# H18R10.net
KiCad netlist of a schematic drawn in EAGLE
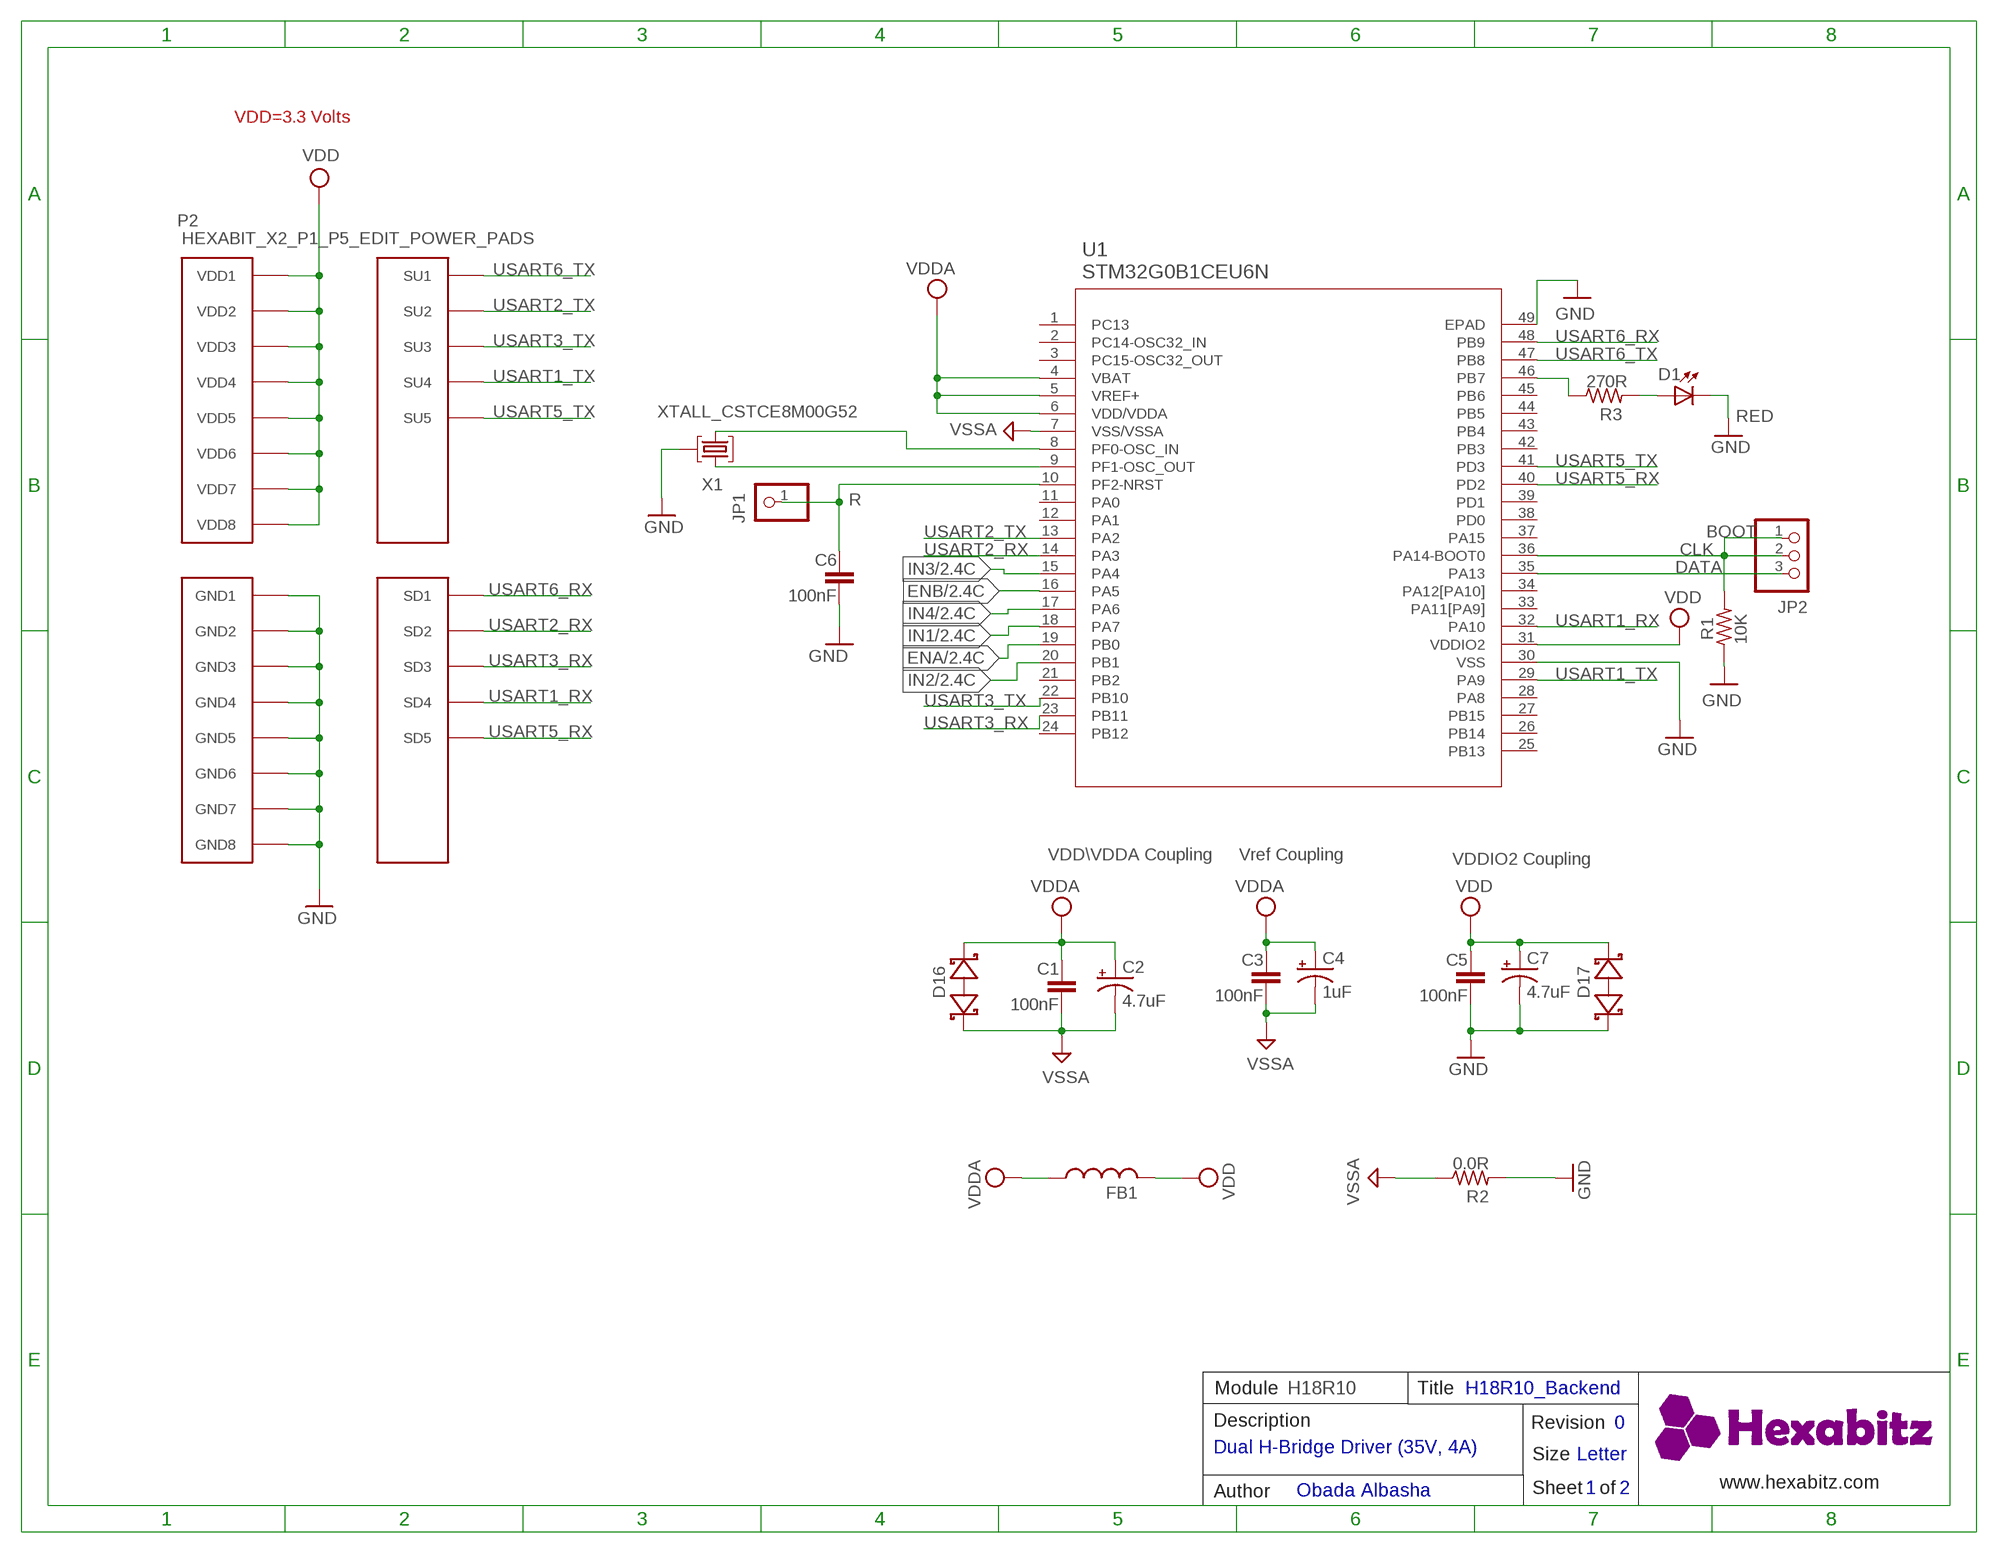
[diagram p0: schematic, sheet 1]
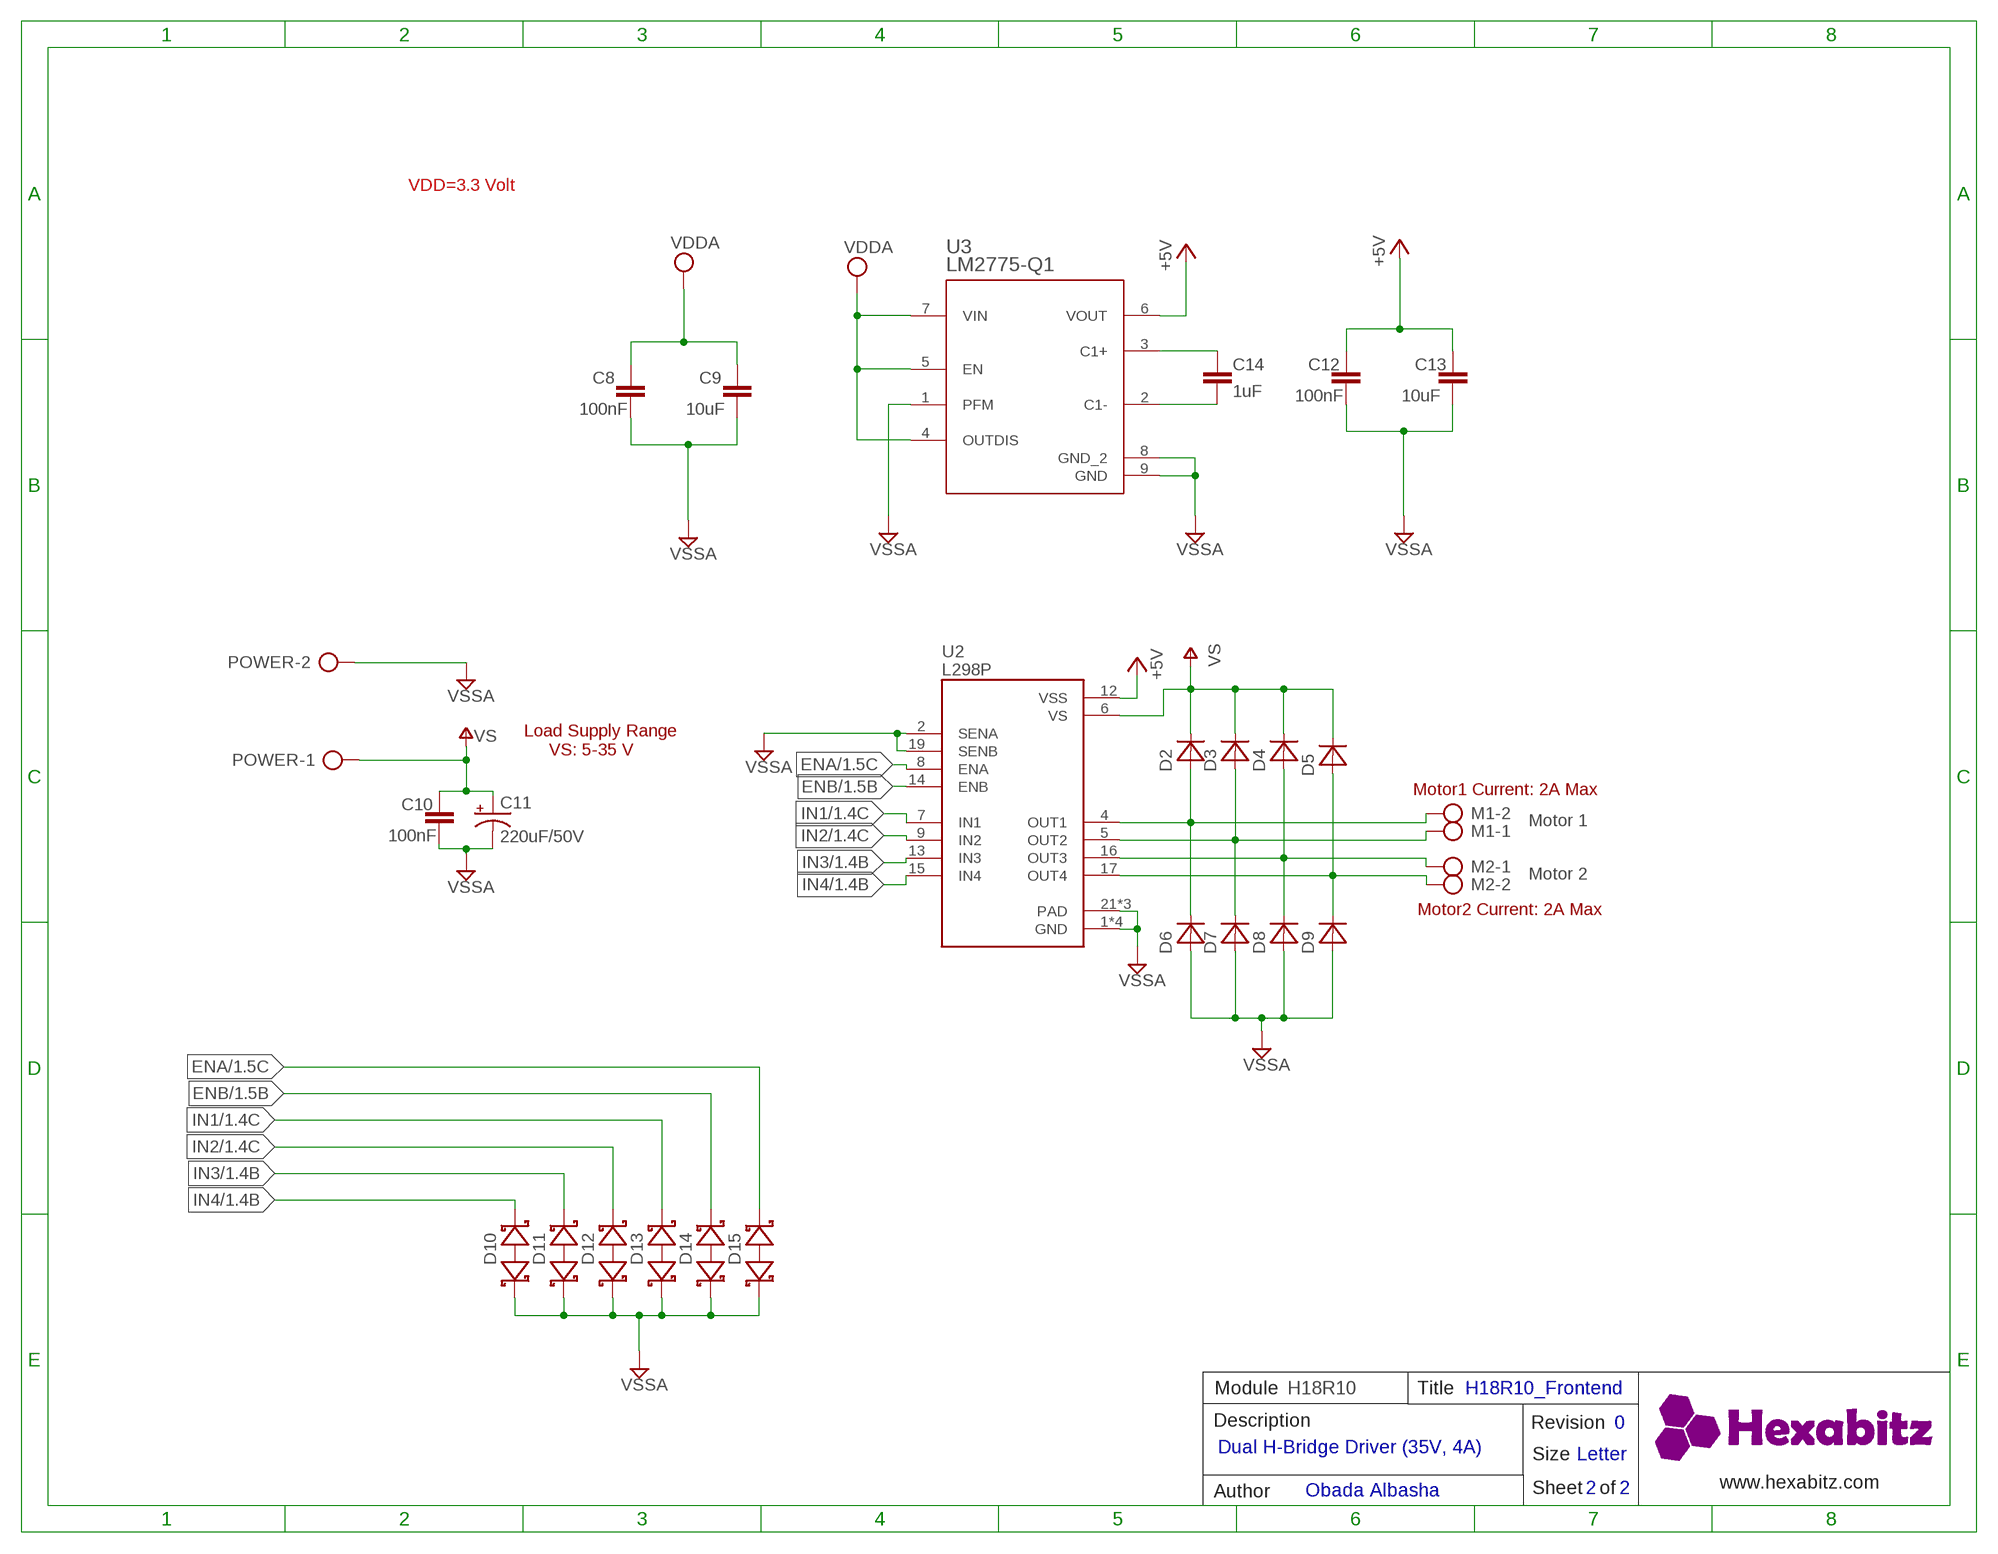
[diagram p1: schematic, sheet 2]

(export (version "E")
  (design (tool "Eeschema 10.0.6"))
  (components
    (comp (ref "C1")
      (value "100nF")
      (footprint "eagle-import:C-0603")
      (libsource (lib "eagle-import") (part "C-0603"))
    )
    (comp (ref "C2")
      (value "4.7uF")
      (footprint "eagle-import:C-0805-POL")
      (libsource (lib "eagle-import") (part "C-0805-POL"))
    )
    (comp (ref "C3")
      (value "100nF")
      (footprint "eagle-import:C-0603")
      (libsource (lib "eagle-import") (part "C-0603"))
    )
    (comp (ref "C4")
      (value "1uF")
      (footprint "eagle-import:C-0805-POL")
      (libsource (lib "eagle-import") (part "C-0805-POL"))
    )
    (comp (ref "C5")
      (value "100nF")
      (footprint "eagle-import:C-0603")
      (libsource (lib "eagle-import") (part "C-0603"))
    )
    (comp (ref "C6")
      (value "100nF")
      (footprint "eagle-import:C-0603")
      (libsource (lib "eagle-import") (part "C-0603"))
    )
    (comp (ref "C7")
      (value "4.7uF")
      (footprint "eagle-import:C-0805-POL")
      (libsource (lib "eagle-import") (part "C-0805-POL"))
    )
    (comp (ref "D1")
      (value "RED")
      (footprint "eagle-import:VLMS1300-GS08")
      (fields
        (field (name "MPN") "VLMS1300-GS08")
        (field (name "MFN") "Vishay")
        (field (name "MPN_1") "VLMS1300-GS08")
        (field (name "OCTOPART_URL") "https://octopart.com/vlms1300-gs08-vishay-21709201?r=sp&s=_gcP4_q8T1SC6PJQPTQ9yA")
      )
      (libsource (lib "eagle-import") (part "VLMS1300-GS08"))
    )
    (comp (ref "D16")
      (value "BOURNS_CDSOD323-T03SCBOURNS_CDSOD323-T03SC_0_0")
      (footprint "eagle-import:BOURNS_CDSOD323-T03SC_0")
      (fields (field (name "MPN") "CDSOD323-T03SC"))
      (libsource (lib "eagle-import") (part "BOURNS_CDSOD323-T03SCBOURNS_CDSOD323-T03SC_0_0"))
    )
    (comp (ref "D17")
      (value "BOURNS_CDSOD323-T03SCBOURNS_CDSOD323-T03SC_0_0")
      (footprint "eagle-import:BOURNS_CDSOD323-T03SC_0")
      (fields (field (name "MPN") "CDSOD323-T03SC"))
      (libsource (lib "eagle-import") (part "BOURNS_CDSOD323-T03SCBOURNS_CDSOD323-T03SC_0_0"))
    )
    (comp (ref "FB1")
      (value "FB-0603")
      (footprint "eagle-import:FB-0603")
      (libsource (lib "eagle-import") (part "FB-0603"))
    )
    (comp (ref "JP1")
      (value "R")
      (footprint "eagle-import:1X01")
      (fields (field (name "MPN") "87227-1"))
      (libsource (lib "eagle-import") (part "PINHD-1X1"))
    )
    (comp (ref "JP2")
      (value "PINHD-1X3")
      (footprint "eagle-import:1X03")
      (libsource (lib "eagle-import") (part "PINHD-1X3"))
    )
    (comp (ref "P2")
      (value "HEXABIT_X2_P1_P5_EDIT_POWER_PADS")
      (footprint "eagle-import:HEXABIT_X2_P1_P5_EDIT_POWER_PADS")
      (libsource (lib "eagle-import") (part "HEXABIT_X2_P1_P5_EDIT_POWER_PADS"))
    )
    (comp (ref "R1")
      (value "10K")
      (footprint "eagle-import:R-0603")
      (libsource (lib "eagle-import") (part "R-0603"))
    )
    (comp (ref "R2")
      (value "0.0R")
      (footprint "eagle-import:R-0603")
      (libsource (lib "eagle-import") (part "R-0603"))
    )
    (comp (ref "R3")
      (value "270R")
      (footprint "eagle-import:R-0603")
      (libsource (lib "eagle-import") (part "R-0603"))
    )
    (comp (ref "U1")
      (value "STM32G0B1CEU6N")
      (footprint "eagle-import:HEXABITZ_ICS_QFN_B1CEU6_STM-L")
      (libsource (lib "eagle-import") (part "STM32G0B1CEU6N"))
    )
    (comp (ref "X1")
      (value "XTALL_CSTCE8M00G52")
      (footprint "eagle-import:XTALL_CSTCE8M00G52")
      (fields (field (name "MPN") "CSTCE8M00G52Z-R0"))
      (libsource (lib "eagle-import") (part "XTALL_CSTCE8M00G52"))
    )
    (comp (ref "C8")
      (value "100nF")
      (footprint "eagle-import:C-0603")
      (libsource (lib "eagle-import") (part "C-0603"))
    )
    (comp (ref "C9")
      (value "10uF")
      (footprint "eagle-import:C-0603")
      (libsource (lib "eagle-import") (part "C-0603"))
    )
    (comp (ref "C10")
      (value "100nF")
      (footprint "eagle-import:C-0603")
      (libsource (lib "eagle-import") (part "C-0603"))
    )
    (comp (ref "C11")
      (value "220uF/50V")
      (footprint "eagle-import:TT5D10")
      (libsource (lib "eagle-import") (part "CPOL-USTT5D10"))
    )
    (comp (ref "C12")
      (value "100nF")
      (footprint "eagle-import:C-0603")
      (libsource (lib "eagle-import") (part "C-0603"))
    )
    (comp (ref "C13")
      (value "10uF")
      (footprint "eagle-import:C-0603")
      (libsource (lib "eagle-import") (part "C-0603"))
    )
    (comp (ref "C14")
      (value "1uF")
      (footprint "eagle-import:C-0603")
      (libsource (lib "eagle-import") (part "C-0603"))
    )
    (comp (ref "D2")
      (value "DIOD-SOD-123")
      (footprint "eagle-import:SOD123")
      (libsource (lib "eagle-import") (part "DIOD-SOD-123"))
    )
    (comp (ref "D3")
      (value "DIOD-SOD-123")
      (footprint "eagle-import:SOD123")
      (libsource (lib "eagle-import") (part "DIOD-SOD-123"))
    )
    (comp (ref "D4")
      (value "DIOD-SOD-123")
      (footprint "eagle-import:SOD123")
      (libsource (lib "eagle-import") (part "DIOD-SOD-123"))
    )
    (comp (ref "D5")
      (value "DIOD-SOD-123")
      (footprint "eagle-import:SOD123")
      (libsource (lib "eagle-import") (part "DIOD-SOD-123"))
    )
    (comp (ref "D6")
      (value "DIOD-SOD-123")
      (footprint "eagle-import:SOD123")
      (libsource (lib "eagle-import") (part "DIOD-SOD-123"))
    )
    (comp (ref "D7")
      (value "DIOD-SOD-123")
      (footprint "eagle-import:SOD123")
      (libsource (lib "eagle-import") (part "DIOD-SOD-123"))
    )
    (comp (ref "D8")
      (value "DIOD-SOD-123")
      (footprint "eagle-import:SOD123")
      (libsource (lib "eagle-import") (part "DIOD-SOD-123"))
    )
    (comp (ref "D9")
      (value "DIOD-SOD-123")
      (footprint "eagle-import:SOD123")
      (libsource (lib "eagle-import") (part "DIOD-SOD-123"))
    )
    (comp (ref "D10")
      (value "BOURNS_CDSOD323-T03SCBOURNS_CDSOD323-T03SC_0_0")
      (footprint "eagle-import:BOURNS_CDSOD323-T03SC_0")
      (fields (field (name "MPN") "CDSOD323-T03SC"))
      (libsource (lib "eagle-import") (part "BOURNS_CDSOD323-T03SCBOURNS_CDSOD323-T03SC_0_0"))
    )
    (comp (ref "D11")
      (value "BOURNS_CDSOD323-T03SCBOURNS_CDSOD323-T03SC_0_0")
      (footprint "eagle-import:BOURNS_CDSOD323-T03SC_0")
      (fields (field (name "MPN") "CDSOD323-T03SC"))
      (libsource (lib "eagle-import") (part "BOURNS_CDSOD323-T03SCBOURNS_CDSOD323-T03SC_0_0"))
    )
    (comp (ref "D12")
      (value "BOURNS_CDSOD323-T03SCBOURNS_CDSOD323-T03SC_0_0")
      (footprint "eagle-import:BOURNS_CDSOD323-T03SC_0")
      (fields (field (name "MPN") "CDSOD323-T03SC"))
      (libsource (lib "eagle-import") (part "BOURNS_CDSOD323-T03SCBOURNS_CDSOD323-T03SC_0_0"))
    )
    (comp (ref "D13")
      (value "BOURNS_CDSOD323-T03SCBOURNS_CDSOD323-T03SC_0_0")
      (footprint "eagle-import:BOURNS_CDSOD323-T03SC_0")
      (fields (field (name "MPN") "CDSOD323-T03SC"))
      (libsource (lib "eagle-import") (part "BOURNS_CDSOD323-T03SCBOURNS_CDSOD323-T03SC_0_0"))
    )
    (comp (ref "D14")
      (value "BOURNS_CDSOD323-T03SCBOURNS_CDSOD323-T03SC_0_0")
      (footprint "eagle-import:BOURNS_CDSOD323-T03SC_0")
      (fields (field (name "MPN") "CDSOD323-T03SC"))
      (libsource (lib "eagle-import") (part "BOURNS_CDSOD323-T03SCBOURNS_CDSOD323-T03SC_0_0"))
    )
    (comp (ref "D15")
      (value "BOURNS_CDSOD323-T03SCBOURNS_CDSOD323-T03SC_0_0")
      (footprint "eagle-import:BOURNS_CDSOD323-T03SC_0")
      (fields (field (name "MPN") "CDSOD323-T03SC"))
      (libsource (lib "eagle-import") (part "BOURNS_CDSOD323-T03SCBOURNS_CDSOD323-T03SC_0_0"))
    )
    (comp (ref "M1")
      (value "AK500/2")
      (footprint "eagle-import:AK500_2")
      (fields (field (name "MPN") "282836-2"))
      (libsource (lib "eagle-import") (part "AK500/2"))
    )
    (comp (ref "M2")
      (value "AK500/2")
      (footprint "eagle-import:AK500_2")
      (fields (field (name "MPN") "282836-2"))
      (libsource (lib "eagle-import") (part "AK500/2"))
    )
    (comp (ref "POWER")
      (value "AK500/2")
      (footprint "eagle-import:AK500_2")
      (fields (field (name "MPN") "282836-2"))
      (libsource (lib "eagle-import") (part "AK500/2"))
    )
    (comp (ref "U2")
      (value "L298P")
      (footprint "eagle-import:SOIC127P1420X360-20N")
      (fields (field (name "MF") "STMicroelectronics"))
      (libsource (lib "eagle-import") (part "L298P"))
    )
    (comp (ref "U3")
      (value "LM2775-Q1")
      (footprint "eagle-import:DSG0008A")
      (fields (field (name "MANUFACTURER") "Texas Instruments") (field (name "MPN") "LM2775QDSGRQ1"))
      (libsource (lib "eagle-import") (part "LM2775QDSGRQ1"))
    )
  )
  (nets
    (net (code "1") (name "+5V") (class "Default")
      (node (ref "C12") (pin "1") (pinfunction "1_1") (pintype "passive"))
      (node (ref "C13") (pin "1") (pinfunction "1_1") (pintype "passive"))
      (node (ref "U2") (pin "12") (pinfunction "VSS_12") (pintype "power_in"))
      (node (ref "U3") (pin "6") (pinfunction "VOUT_6") (pintype "power_in"))
    )
    (net (code "2") (name "CLK") (class "Default")
      (node (ref "JP2") (pin "1") (pinfunction "1_1") (pintype "passive"))
      (node (ref "JP2") (pin "2") (pinfunction "2_2") (pintype "passive"))
      (node (ref "R1") (pin "2") (pinfunction "2_2") (pintype "passive"))
      (node (ref "U1") (pin "36") (pinfunction "PA14-BOOT0_36") (pintype "bidirectional"))
    )
    (net (code "3") (name "DATA") (class "Default")
      (node (ref "JP2") (pin "3") (pinfunction "3_3") (pintype "passive"))
      (node (ref "U1") (pin "35") (pinfunction "PA13_35") (pintype "bidirectional"))
    )
    (net (code "4") (name "ENA") (class "Default")
      (node (ref "D15") (pin "2") (pinfunction "C_2") (pintype "passive"))
      (node (ref "U1") (pin "19") (pinfunction "PB0_19") (pintype "bidirectional"))
      (node (ref "U2") (pin "8") (pinfunction "ENA_8") (pintype "input"))
    )
    (net (code "5") (name "ENB") (class "Default")
      (node (ref "D14") (pin "2") (pinfunction "C_2") (pintype "passive"))
      (node (ref "U1") (pin "16") (pinfunction "PA5_16") (pintype "bidirectional"))
      (node (ref "U2") (pin "14") (pinfunction "ENB_14") (pintype "input"))
    )
    (net (code "6") (name "GND") (class "Default")
      (node (ref "C5") (pin "2") (pinfunction "2_2") (pintype "passive"))
      (node (ref "C6") (pin "2") (pinfunction "2_2") (pintype "passive"))
      (node (ref "C7") (pin "2") (pinfunction "-_2") (pintype "passive"))
      (node (ref "D1") (pin "C") (pinfunction "C_C") (pintype "passive"))
      (node (ref "D17") (pin "1") (pinfunction "A_1") (pintype "passive"))
      (node (ref "P2") (pin "PAD_PD11") (pinfunction "GND1_PAD_PD11") (pintype "power_in"))
      (node (ref "P2") (pin "PAD_PD12") (pinfunction "GND2_PAD_PD12") (pintype "power_in"))
      (node (ref "P2") (pin "PAD_PD13") (pinfunction "GND3_PAD_PD13") (pintype "power_in"))
      (node (ref "P2") (pin "PAD_PD14") (pinfunction "GND4_PAD_PD14") (pintype "power_in"))
      (node (ref "P2") (pin "PAD_PD17") (pinfunction "GND5_PAD_PD17") (pintype "power_in"))
      (node (ref "P2") (pin "PAD_PD18") (pinfunction "GND6_PAD_PD18") (pintype "power_in"))
      (node (ref "P2") (pin "PAD_PD19") (pinfunction "GND7_PAD_PD19") (pintype "power_in"))
      (node (ref "P2") (pin "PAD_PD20") (pinfunction "GND8_PAD_PD20") (pintype "power_in"))
      (node (ref "R1") (pin "1") (pinfunction "1_1") (pintype "passive"))
      (node (ref "R2") (pin "2") (pinfunction "2_2") (pintype "passive"))
      (node (ref "U1") (pin "30") (pinfunction "VSS_30") (pintype "passive"))
      (node (ref "U1") (pin "49") (pinfunction "EPAD_49") (pintype "passive"))
      (node (ref "X1") (pin "P$2") (pinfunction "2_P$2") (pintype "passive"))
    )
    (net (code "7") (name "IN1") (class "Default")
      (node (ref "D13") (pin "2") (pinfunction "C_2") (pintype "passive"))
      (node (ref "U1") (pin "18") (pinfunction "PA7_18") (pintype "bidirectional"))
      (node (ref "U2") (pin "7") (pinfunction "IN1_7") (pintype "input"))
    )
    (net (code "8") (name "IN2") (class "Default")
      (node (ref "D12") (pin "2") (pinfunction "C_2") (pintype "passive"))
      (node (ref "U1") (pin "20") (pinfunction "PB1_20") (pintype "bidirectional"))
      (node (ref "U2") (pin "9") (pinfunction "IN2_9") (pintype "input"))
    )
    (net (code "9") (name "IN3") (class "Default")
      (node (ref "D11") (pin "2") (pinfunction "C_2") (pintype "passive"))
      (node (ref "U1") (pin "15") (pinfunction "PA4_15") (pintype "bidirectional"))
      (node (ref "U2") (pin "13") (pinfunction "IN3_13") (pintype "input"))
    )
    (net (code "10") (name "IN4") (class "Default")
      (node (ref "D10") (pin "2") (pinfunction "C_2") (pintype "passive"))
      (node (ref "U1") (pin "17") (pinfunction "PA6_17") (pintype "bidirectional"))
      (node (ref "U2") (pin "15") (pinfunction "IN4_15") (pintype "input"))
    )
    (net (code "11") (name "Net-(D1-PadA)") (class "Default")
      (node (ref "D1") (pin "A") (pinfunction "A_A") (pintype "passive"))
      (node (ref "R3") (pin "2") (pinfunction "2_2") (pintype "passive"))
    )
    (net (code "12") (name "Net-(D2-A)") (class "Default")
      (node (ref "D2") (pin "1") (pinfunction "A_1") (pintype "passive"))
      (node (ref "D6") (pin "2") (pinfunction "C_2") (pintype "passive"))
      (node (ref "M1") (pin "2") (pinfunction "KL_2") (pintype "passive"))
      (node (ref "U2") (pin "4") (pinfunction "OUT1_4") (pintype "output"))
    )
    (net (code "13") (name "Net-(D3-A)") (class "Default")
      (node (ref "D3") (pin "1") (pinfunction "A_1") (pintype "passive"))
      (node (ref "D7") (pin "2") (pinfunction "C_2") (pintype "passive"))
      (node (ref "M1") (pin "1") (pinfunction "KL_1") (pintype "passive"))
      (node (ref "U2") (pin "5") (pinfunction "OUT2_5") (pintype "output"))
    )
    (net (code "14") (name "Net-(D4-A)") (class "Default")
      (node (ref "D4") (pin "1") (pinfunction "A_1") (pintype "passive"))
      (node (ref "D8") (pin "2") (pinfunction "C_2") (pintype "passive"))
      (node (ref "M2") (pin "1") (pinfunction "KL_1") (pintype "passive"))
      (node (ref "U2") (pin "16") (pinfunction "OUT3_16") (pintype "output"))
    )
    (net (code "15") (name "Net-(D5-A)") (class "Default")
      (node (ref "D5") (pin "1") (pinfunction "A_1") (pintype "passive"))
      (node (ref "D9") (pin "2") (pinfunction "C_2") (pintype "passive"))
      (node (ref "M2") (pin "2") (pinfunction "KL_2") (pintype "passive"))
      (node (ref "U2") (pin "17") (pinfunction "OUT4_17") (pintype "output"))
    )
    (net (code "16") (name "Net-(U1-PB7)") (class "Default")
      (node (ref "R3") (pin "1") (pinfunction "1_1") (pintype "passive"))
      (node (ref "U1") (pin "46") (pinfunction "PB7_46") (pintype "bidirectional"))
    )
    (net (code "17") (name "Net-(U1-PF0-OSC_IN)") (class "Default")
      (node (ref "U1") (pin "8") (pinfunction "PF0-OSC_IN_8") (pintype "bidirectional"))
      (node (ref "X1") (pin "P$3") (pinfunction "3_P$3") (pintype "passive"))
    )
    (net (code "18") (name "Net-(U1-PF1-OSC_OUT)") (class "Default")
      (node (ref "U1") (pin "9") (pinfunction "PF1-OSC_OUT_9") (pintype "bidirectional"))
      (node (ref "X1") (pin "P$1") (pinfunction "1_P$1") (pintype "passive"))
    )
    (net (code "19") (name "Net-(U1-PF2-NRST)") (class "Default")
      (node (ref "C6") (pin "1") (pinfunction "1_1") (pintype "passive"))
      (node (ref "JP1") (pin "1") (pinfunction "1_1") (pintype "passive"))
      (node (ref "U1") (pin "10") (pinfunction "PF2-NRST_10") (pintype "bidirectional"))
    )
    (net (code "20") (name "Net-(U3-C1+)") (class "Default")
      (node (ref "C14") (pin "1") (pinfunction "1_1") (pintype "passive"))
      (node (ref "U3") (pin "3") (pinfunction "C1+_3") (pintype "power_in"))
    )
    (net (code "21") (name "Net-(U3-C1-)") (class "Default")
      (node (ref "C14") (pin "2") (pinfunction "2_2") (pintype "passive"))
      (node (ref "U3") (pin "2") (pinfunction "C1-_2") (pintype "power_in"))
    )
    (net (code "22") (name "USART1_RX") (class "Default")
      (node (ref "P2") (pin "PAD_PD4") (pinfunction "SD4_PAD_PD4") (pintype "bidirectional"))
      (node (ref "U1") (pin "32") (pinfunction "PA10_32") (pintype "bidirectional"))
    )
    (net (code "23") (name "USART1_TX") (class "Default")
      (node (ref "P2") (pin "PAD_PU4") (pinfunction "SU4_PAD_PU4") (pintype "bidirectional"))
      (node (ref "U1") (pin "29") (pinfunction "PA9_29") (pintype "bidirectional"))
    )
    (net (code "24") (name "USART2_RX") (class "Default")
      (node (ref "P2") (pin "PAD_PD2") (pinfunction "SD2_PAD_PD2") (pintype "bidirectional"))
      (node (ref "U1") (pin "14") (pinfunction "PA3_14") (pintype "bidirectional"))
    )
    (net (code "25") (name "USART2_TX") (class "Default")
      (node (ref "P2") (pin "PAD_PU2") (pinfunction "SU2_PAD_PU2") (pintype "bidirectional"))
      (node (ref "U1") (pin "13") (pinfunction "PA2_13") (pintype "bidirectional"))
    )
    (net (code "26") (name "USART3_RX") (class "Default")
      (node (ref "P2") (pin "PAD_PD3") (pinfunction "SD3_PAD_PD3") (pintype "bidirectional"))
      (node (ref "U1") (pin "23") (pinfunction "PB11_23") (pintype "bidirectional"))
    )
    (net (code "27") (name "USART3_TX") (class "Default")
      (node (ref "P2") (pin "PAD_PU3") (pinfunction "SU3_PAD_PU3") (pintype "bidirectional"))
      (node (ref "U1") (pin "22") (pinfunction "PB10_22") (pintype "bidirectional"))
    )
    (net (code "28") (name "USART5_RX") (class "Default")
      (node (ref "P2") (pin "PAD_PD5") (pinfunction "SD5_PAD_PD5") (pintype "bidirectional"))
      (node (ref "U1") (pin "40") (pinfunction "PD2_40") (pintype "bidirectional"))
    )
    (net (code "29") (name "USART5_TX") (class "Default")
      (node (ref "P2") (pin "PAD_PU5") (pinfunction "SU5_PAD_PU5") (pintype "bidirectional"))
      (node (ref "U1") (pin "41") (pinfunction "PD3_41") (pintype "bidirectional"))
    )
    (net (code "30") (name "USART6_RX") (class "Default")
      (node (ref "P2") (pin "PAD_PD1") (pinfunction "SD1_PAD_PD1") (pintype "bidirectional"))
      (node (ref "U1") (pin "48") (pinfunction "PB9_48") (pintype "bidirectional"))
    )
    (net (code "31") (name "USART6_TX") (class "Default")
      (node (ref "P2") (pin "PAD_PU1") (pinfunction "SU1_PAD_PU1") (pintype "bidirectional"))
      (node (ref "U1") (pin "47") (pinfunction "PB8_47") (pintype "bidirectional"))
    )
    (net (code "32") (name "V+") (class "Default")
      (node (ref "C10") (pin "1") (pinfunction "1_1") (pintype "passive"))
      (node (ref "C11") (pin "+") (pinfunction "+_+") (pintype "passive"))
      (node (ref "D2") (pin "2") (pinfunction "C_2") (pintype "passive"))
      (node (ref "D3") (pin "2") (pinfunction "C_2") (pintype "passive"))
      (node (ref "D4") (pin "2") (pinfunction "C_2") (pintype "passive"))
      (node (ref "D5") (pin "2") (pinfunction "C_2") (pintype "passive"))
      (node (ref "POWER") (pin "1") (pinfunction "KL_1") (pintype "passive"))
      (node (ref "U2") (pin "6") (pinfunction "VS_6") (pintype "power_in"))
    )
    (net (code "33") (name "VDD") (class "Default")
      (node (ref "C5") (pin "1") (pinfunction "1_1") (pintype "passive"))
      (node (ref "C7") (pin "1") (pinfunction "+_1") (pintype "passive"))
      (node (ref "D17") (pin "2") (pinfunction "C_2") (pintype "passive"))
      (node (ref "FB1") (pin "2") (pinfunction "2_2") (pintype "passive"))
      (node (ref "P2") (pin "PAD_PU11") (pinfunction "VDD1_PAD_PU11") (pintype "power_in"))
      (node (ref "P2") (pin "PAD_PU12") (pinfunction "VDD2_PAD_PU12") (pintype "power_in"))
      (node (ref "P2") (pin "PAD_PU13") (pinfunction "VDD3_PAD_PU13") (pintype "power_in"))
      (node (ref "P2") (pin "PAD_PU14") (pinfunction "VDD4_PAD_PU14") (pintype "power_in"))
      (node (ref "P2") (pin "PAD_PU17") (pinfunction "VDD5_PAD_PU17") (pintype "power_in"))
      (node (ref "P2") (pin "PAD_PU18") (pinfunction "VDD6_PAD_PU18") (pintype "power_in"))
      (node (ref "P2") (pin "PAD_PU19") (pinfunction "VDD7_PAD_PU19") (pintype "power_in"))
      (node (ref "P2") (pin "PAD_PU20") (pinfunction "VDD8_PAD_PU20") (pintype "power_in"))
      (node (ref "U1") (pin "31") (pinfunction "VDDIO2_31") (pintype "power_in"))
    )
    (net (code "34") (name "VDDA") (class "Default")
      (node (ref "C1") (pin "1") (pinfunction "1_1") (pintype "passive"))
      (node (ref "C2") (pin "1") (pinfunction "+_1") (pintype "passive"))
      (node (ref "C3") (pin "1") (pinfunction "1_1") (pintype "passive"))
      (node (ref "C4") (pin "1") (pinfunction "+_1") (pintype "passive"))
      (node (ref "C8") (pin "1") (pinfunction "1_1") (pintype "passive"))
      (node (ref "C9") (pin "1") (pinfunction "1_1") (pintype "passive"))
      (node (ref "D16") (pin "2") (pinfunction "C_2") (pintype "passive"))
      (node (ref "FB1") (pin "1") (pinfunction "1_1") (pintype "passive"))
      (node (ref "U1") (pin "4") (pinfunction "VBAT_4") (pintype "power_in"))
      (node (ref "U1") (pin "5") (pinfunction "VREF+_5") (pintype "power_in"))
      (node (ref "U1") (pin "6") (pinfunction "VDD/VDDA_6") (pintype "power_in"))
      (node (ref "U3") (pin "4") (pinfunction "OUTDIS_4") (pintype "input"))
      (node (ref "U3") (pin "5") (pinfunction "EN_5") (pintype "input"))
      (node (ref "U3") (pin "7") (pinfunction "VIN_7") (pintype "power_in"))
    )
    (net (code "35") (name "VSSA") (class "Default")
      (node (ref "C1") (pin "2") (pinfunction "2_2") (pintype "passive"))
      (node (ref "C10") (pin "2") (pinfunction "2_2") (pintype "passive"))
      (node (ref "C11") (pin "-") (pinfunction "-_-") (pintype "passive"))
      (node (ref "C12") (pin "2") (pinfunction "2_2") (pintype "passive"))
      (node (ref "C13") (pin "2") (pinfunction "2_2") (pintype "passive"))
      (node (ref "C2") (pin "2") (pinfunction "-_2") (pintype "passive"))
      (node (ref "C3") (pin "2") (pinfunction "2_2") (pintype "passive"))
      (node (ref "C4") (pin "2") (pinfunction "-_2") (pintype "passive"))
      (node (ref "C8") (pin "2") (pinfunction "2_2") (pintype "passive"))
      (node (ref "C9") (pin "2") (pinfunction "2_2") (pintype "passive"))
      (node (ref "D10") (pin "1") (pinfunction "A_1") (pintype "passive"))
      (node (ref "D11") (pin "1") (pinfunction "A_1") (pintype "passive"))
      (node (ref "D12") (pin "1") (pinfunction "A_1") (pintype "passive"))
      (node (ref "D13") (pin "1") (pinfunction "A_1") (pintype "passive"))
      (node (ref "D14") (pin "1") (pinfunction "A_1") (pintype "passive"))
      (node (ref "D15") (pin "1") (pinfunction "A_1") (pintype "passive"))
      (node (ref "D16") (pin "1") (pinfunction "A_1") (pintype "passive"))
      (node (ref "D6") (pin "1") (pinfunction "A_1") (pintype "passive"))
      (node (ref "D7") (pin "1") (pinfunction "A_1") (pintype "passive"))
      (node (ref "D8") (pin "1") (pinfunction "A_1") (pintype "passive"))
      (node (ref "D9") (pin "1") (pinfunction "A_1") (pintype "passive"))
      (node (ref "POWER") (pin "2") (pinfunction "KL_2") (pintype "passive"))
      (node (ref "R2") (pin "1") (pinfunction "1_1") (pintype "passive"))
      (node (ref "U1") (pin "7") (pinfunction "VSS/VSSA_7") (pintype "passive"))
      (node (ref "U2") (pin "1") (pinfunction "GND_1") (pintype "passive"))
      (node (ref "U2") (pin "10") (pinfunction "GND_10") (pintype "passive"))
      (node (ref "U2") (pin "11") (pinfunction "GND_11") (pintype "passive"))
      (node (ref "U2") (pin "19") (pinfunction "SENB_19") (pintype "input"))
      (node (ref "U2") (pin "2") (pinfunction "SENA_2") (pintype "input"))
      (node (ref "U2") (pin "20") (pinfunction "GND_20") (pintype "passive"))
      (node (ref "U2") (pin "21") (pinfunction "PAD_21") (pintype "passive"))
      (node (ref "U2") (pin "22") (pinfunction "PAD_22") (pintype "passive"))
      (node (ref "U2") (pin "23") (pinfunction "PAD_23") (pintype "passive"))
      (node (ref "U3") (pin "1") (pinfunction "PFM_1") (pintype "input"))
      (node (ref "U3") (pin "8") (pinfunction "GND_2_8") (pintype "power_in"))
      (node (ref "U3") (pin "9") (pinfunction "GND_9") (pintype "power_in"))
    )
    (net (code "36") (name "unconnected-(U1-PA0-Pad11)") (class "Default")
      (node (ref "U1") (pin "11") (pinfunction "PA0_11") (pintype "bidirectional"))
    )
    (net (code "37") (name "unconnected-(U1-PA1-Pad12)") (class "Default")
      (node (ref "U1") (pin "12") (pinfunction "PA1_12") (pintype "bidirectional"))
    )
    (net (code "38") (name "unconnected-(U1-PA8-Pad28)") (class "Default")
      (node (ref "U1") (pin "28") (pinfunction "PA8_28") (pintype "bidirectional"))
    )
    (net (code "39") (name "unconnected-(U1-PA11[PA9]-Pad33)") (class "Default")
      (node (ref "U1") (pin "33") (pinfunction "PA11[PA9]_33") (pintype "bidirectional"))
    )
    (net (code "40") (name "unconnected-(U1-PA12[PA10]-Pad34)") (class "Default")
      (node (ref "U1") (pin "34") (pinfunction "PA12[PA10]_34") (pintype "bidirectional"))
    )
    (net (code "41") (name "unconnected-(U1-PA15-Pad37)") (class "Default")
      (node (ref "U1") (pin "37") (pinfunction "PA15_37") (pintype "bidirectional"))
    )
    (net (code "42") (name "unconnected-(U1-PB2-Pad21)") (class "Default")
      (node (ref "U1") (pin "21") (pinfunction "PB2_21") (pintype "bidirectional"))
    )
    (net (code "43") (name "unconnected-(U1-PB3-Pad42)") (class "Default")
      (node (ref "U1") (pin "42") (pinfunction "PB3_42") (pintype "bidirectional"))
    )
    (net (code "44") (name "unconnected-(U1-PB4-Pad43)") (class "Default")
      (node (ref "U1") (pin "43") (pinfunction "PB4_43") (pintype "bidirectional"))
    )
    (net (code "45") (name "unconnected-(U1-PB5-Pad44)") (class "Default")
      (node (ref "U1") (pin "44") (pinfunction "PB5_44") (pintype "bidirectional"))
    )
    (net (code "46") (name "unconnected-(U1-PB6-Pad45)") (class "Default")
      (node (ref "U1") (pin "45") (pinfunction "PB6_45") (pintype "bidirectional"))
    )
    (net (code "47") (name "unconnected-(U1-PB12-Pad24)") (class "Default")
      (node (ref "U1") (pin "24") (pinfunction "PB12_24") (pintype "bidirectional"))
    )
    (net (code "48") (name "unconnected-(U1-PB13-Pad25)") (class "Default")
      (node (ref "U1") (pin "25") (pinfunction "PB13_25") (pintype "bidirectional"))
    )
    (net (code "49") (name "unconnected-(U1-PB14-Pad26)") (class "Default")
      (node (ref "U1") (pin "26") (pinfunction "PB14_26") (pintype "bidirectional"))
    )
    (net (code "50") (name "unconnected-(U1-PB15-Pad27)") (class "Default")
      (node (ref "U1") (pin "27") (pinfunction "PB15_27") (pintype "bidirectional"))
    )
    (net (code "51") (name "unconnected-(U1-PC13-Pad1)") (class "Default")
      (node (ref "U1") (pin "1") (pinfunction "PC13_1") (pintype "bidirectional"))
    )
    (net (code "52") (name "unconnected-(U1-PC14-OSC32_IN-Pad2)") (class "Default")
      (node (ref "U1") (pin "2") (pinfunction "PC14-OSC32_IN_2") (pintype "bidirectional"))
    )
    (net (code "53") (name "unconnected-(U1-PC15-OSC32_OUT-Pad3)") (class "Default")
      (node (ref "U1") (pin "3") (pinfunction "PC15-OSC32_OUT_3") (pintype "bidirectional"))
    )
    (net (code "54") (name "unconnected-(U1-PD0-Pad38)") (class "Default")
      (node (ref "U1") (pin "38") (pinfunction "PD0_38") (pintype "bidirectional"))
    )
    (net (code "55") (name "unconnected-(U1-PD1-Pad39)") (class "Default")
      (node (ref "U1") (pin "39") (pinfunction "PD1_39") (pintype "bidirectional"))
    )
  )
)
